# SCH_sunbeam-card_2026-07-29.net
KiCad netlist of a schematic drawn in EasyEDA
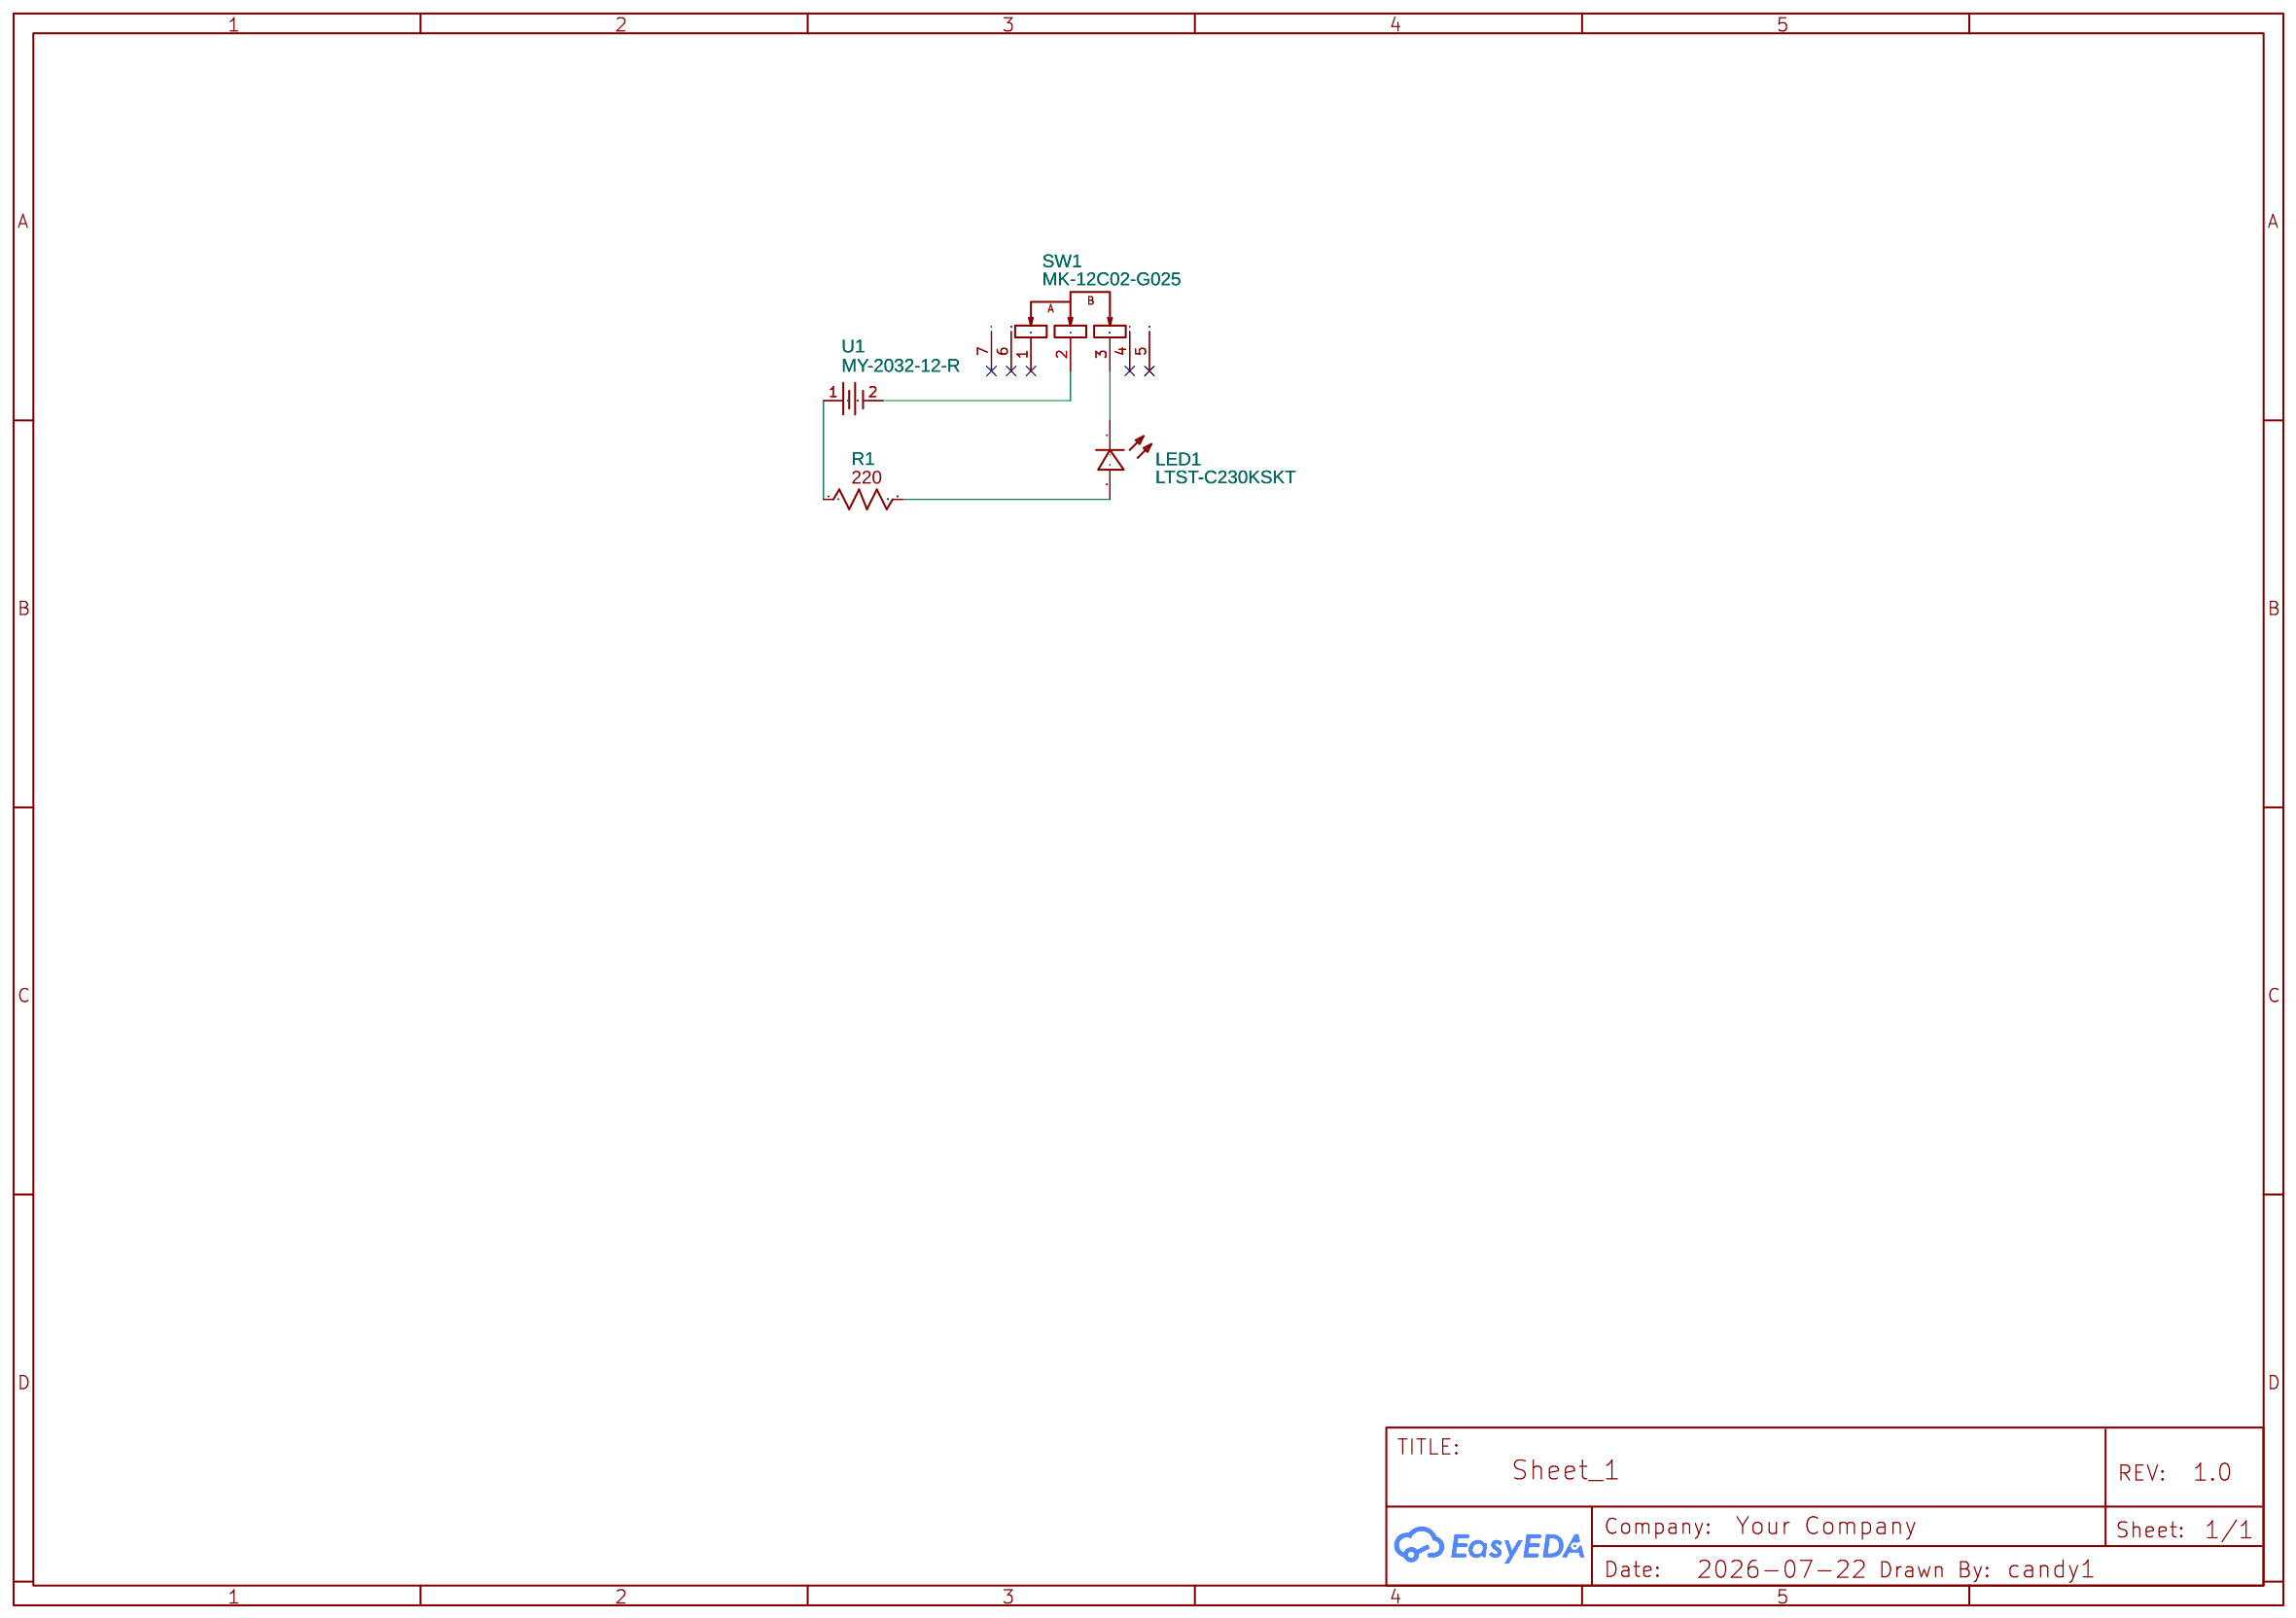
[diagram p0: schematic sheet]

(export (version "E")
  (design (tool "Eeschema 10.0.6"))
  (components
    (comp (ref "LED1")
      (value "LTST-C230KSKT")
      (fields (field (name "Manufacturer") "LITEON(光宝)"))
      (libsource (lib "") (part "LTST-C230KSKT"))
    )
    (comp (ref "R1")
      (value "220 Ohm (0603)")
      (fields
        (field (name "Manufacturer Part") "71-CRCW060320K0FKEAC")
        (field (name "Manufacturer") "Vishay/Dale")
      )
      (libsource (lib "") (part "20k Ohm Resistor (0603) SMD - CRCW060320K0FKEAC"))
    )
    (comp (ref "SW1")
      (value "MK-12C02-G025")
      (fields (field (name "Manufacturer") "G-Switch(品赞)"))
      (libsource (lib "") (part "MK-12C02-G025"))
    )
    (comp (ref "U1")
      (value "MY-2032-12-R")
      (fields (field (name "Manufacturer") "MYOUNG(美阳)"))
      (libsource (lib "") (part "MY-2032-12-R"))
    )
  )
  (nets
    (net (code "1") (name "Net-(LED1-+)") (class "Default")
      (node (ref "LED1") (pin "2") (pinfunction "+_2") (pintype "unspecified"))
      (node (ref "R1") (pin "2") (pinfunction "2_2") (pintype "unspecified"))
    )
    (net (code "2") (name "Net-(LED1--)") (class "Default")
      (node (ref "LED1") (pin "1") (pinfunction "-_1") (pintype "unspecified"))
      (node (ref "SW1") (pin "3") (pinfunction "3_3") (pintype "unspecified"))
    )
    (net (code "3") (name "Net-(U1-BAT+)") (class "Default")
      (node (ref "R1") (pin "1") (pinfunction "1_1") (pintype "unspecified"))
      (node (ref "U1") (pin "1") (pinfunction "BAT+_1") (pintype "input"))
    )
    (net (code "4") (name "Net-(U1-BAT-)") (class "Default")
      (node (ref "SW1") (pin "2") (pinfunction "2_2") (pintype "unspecified"))
      (node (ref "U1") (pin "2") (pinfunction "BAT-_2") (pintype "input"))
    )
    (net (code "5") (name "unconnected-(SW1-Pad1)") (class "Default")
      (node (ref "SW1") (pin "1") (pinfunction "1_1") (pintype "unspecified+no_connect"))
    )
    (net (code "6") (name "unconnected-(SW1-Pad4)") (class "Default")
      (node (ref "SW1") (pin "4") (pinfunction "4_4") (pintype "unspecified+no_connect"))
    )
    (net (code "7") (name "unconnected-(SW1-Pad5)") (class "Default")
      (node (ref "SW1") (pin "5") (pinfunction "5_5") (pintype "unspecified+no_connect"))
    )
    (net (code "8") (name "unconnected-(SW1-Pad6)") (class "Default")
      (node (ref "SW1") (pin "6") (pinfunction "6_6") (pintype "unspecified+no_connect"))
    )
    (net (code "9") (name "unconnected-(SW1-Pad7)") (class "Default")
      (node (ref "SW1") (pin "7") (pinfunction "7_7") (pintype "unspecified+no_connect"))
    )
  )
)
